# design.net
KiCad netlist of a schematic drawn in EasyEDA Pro
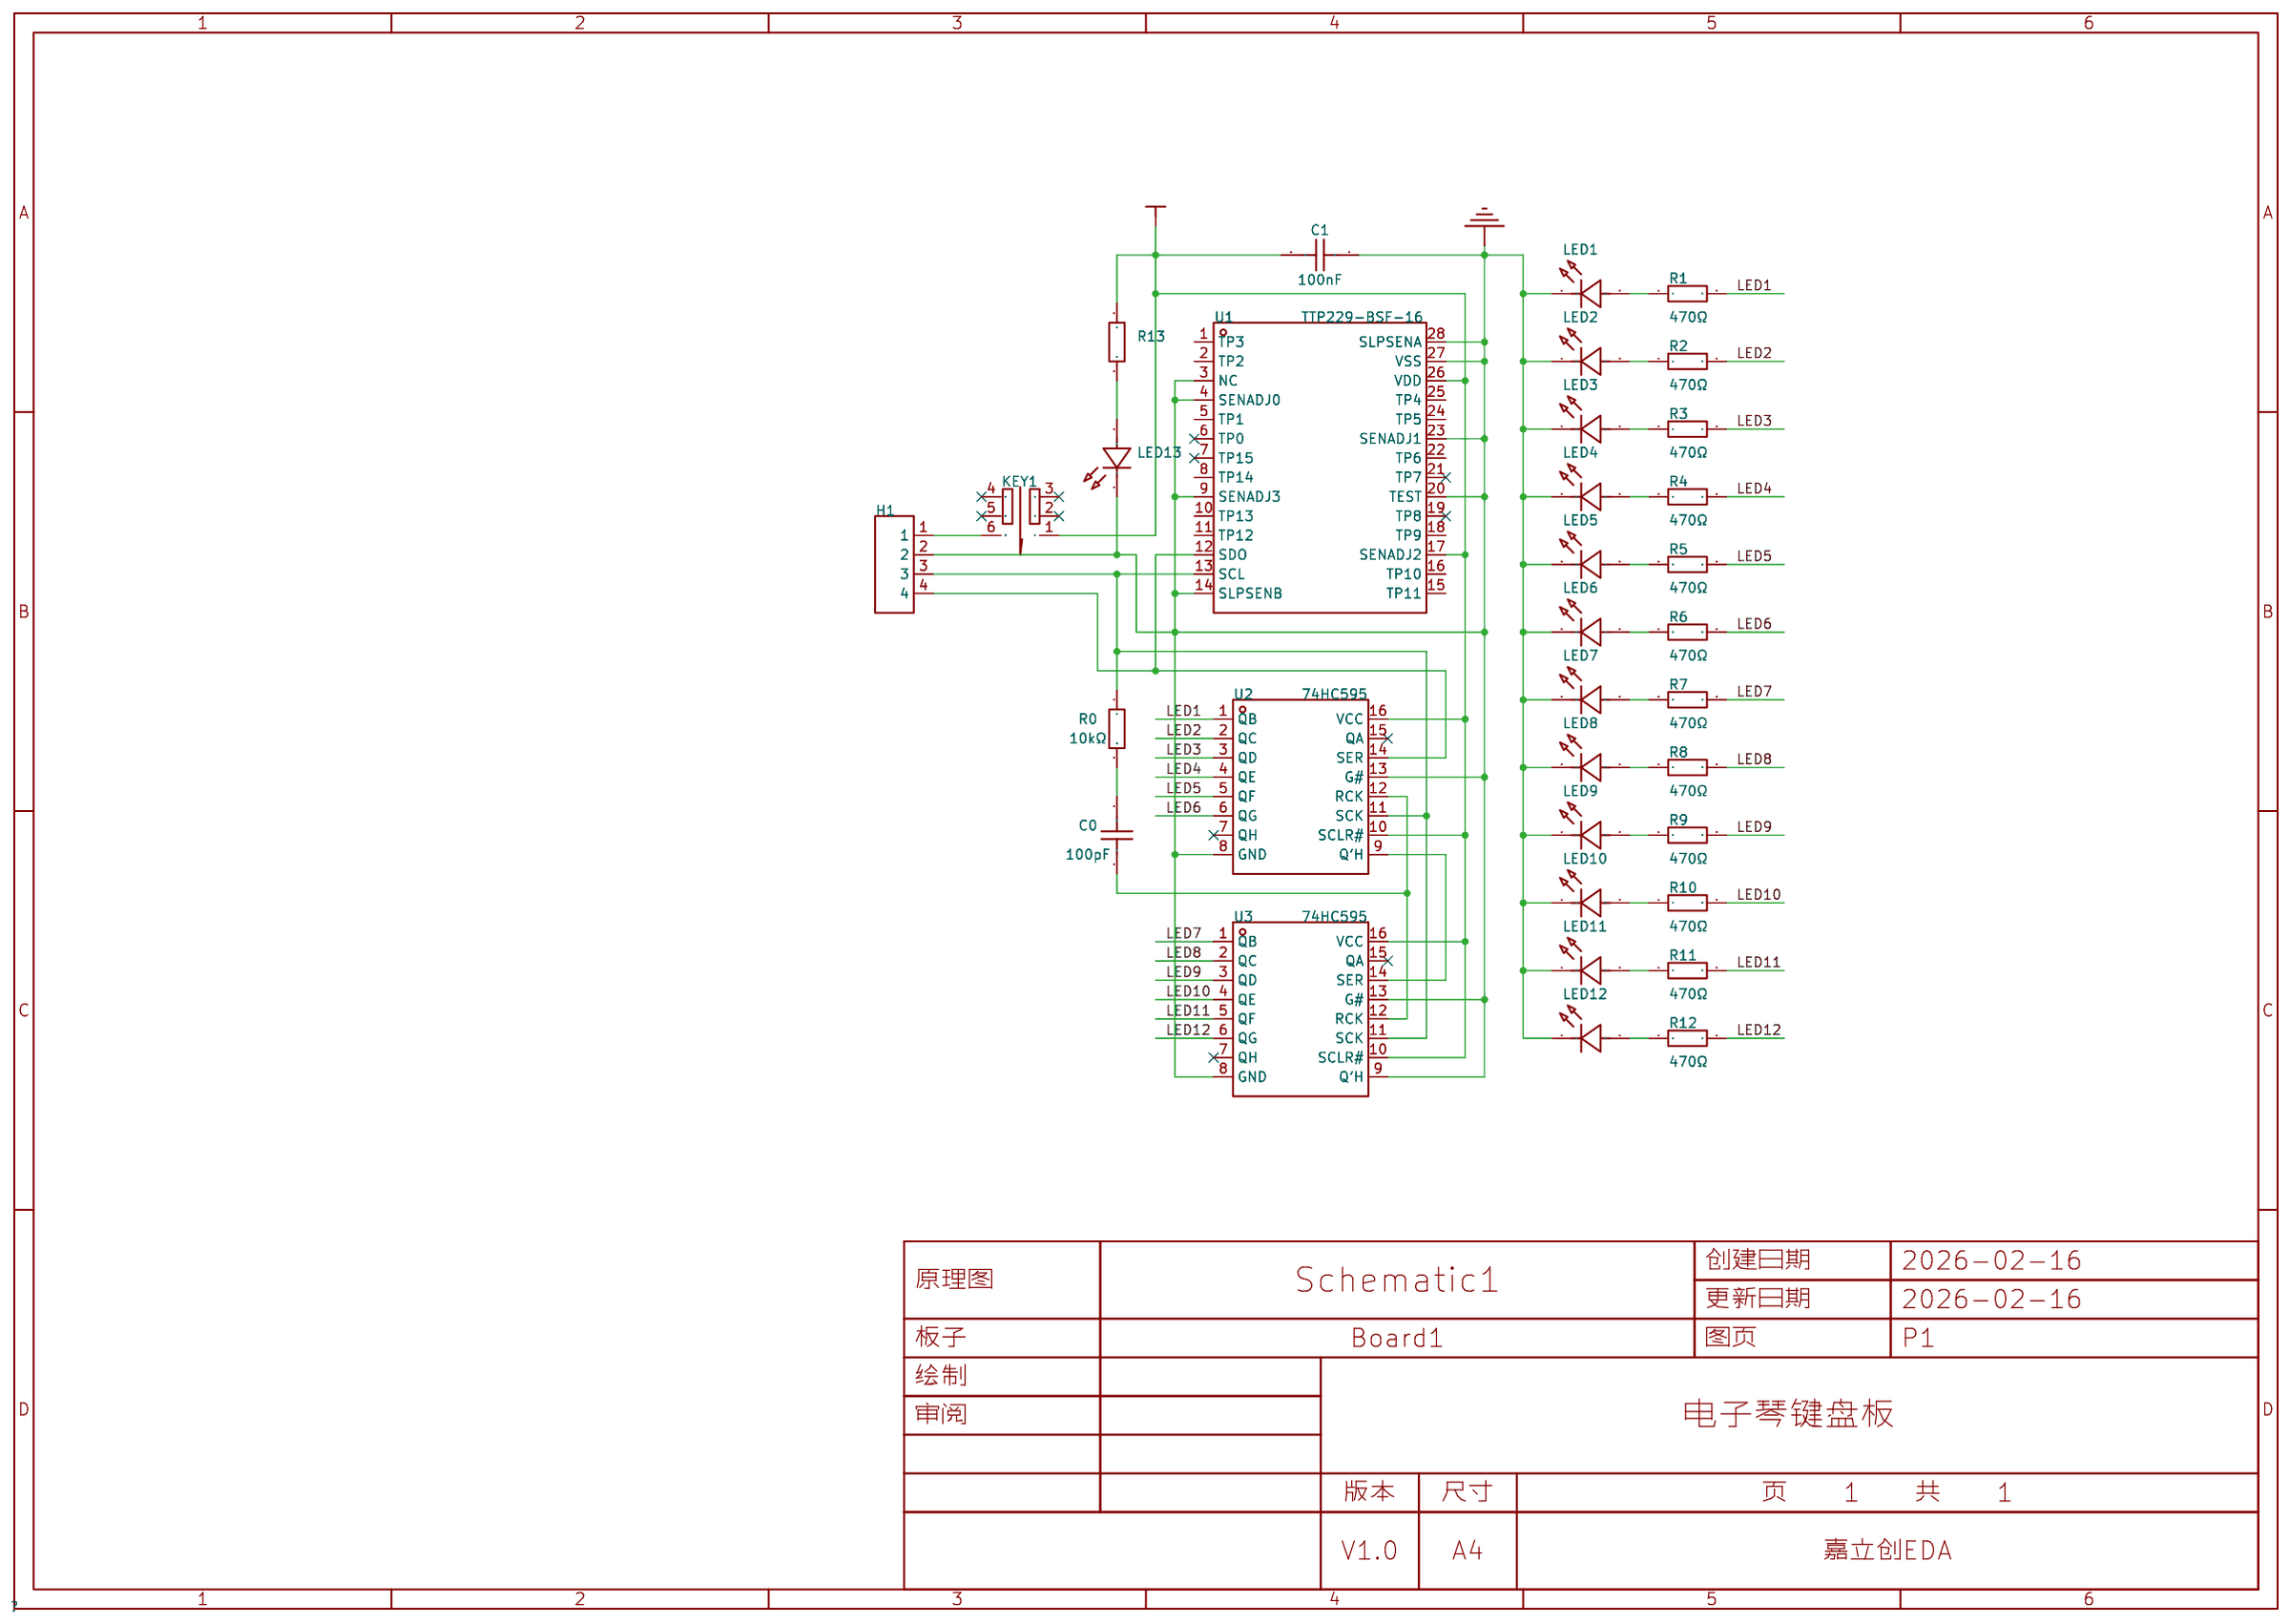
[diagram p0: schematic sheet]

(export (version "E")
  (design (tool "Eeschema 10.0.6"))
  (components
    (comp (ref "C0")
      (value "100pF")
      (footprint "easyedapro:C0603")
      (fields
        (field (name "Manufacturer Part") "CC0603JRNPO9BN101")
        (field (name "Manufacturer") "YAGEO(国巨)")
      )
      (libsource (lib "easyedapro") (part "CC0603JRNPO9BN101"))
    )
    (comp (ref "C1")
      (value "100nF")
      (footprint "easyedapro:C0603")
      (fields
        (field (name "Manufacturer Part") "CGA0603X7R104K500JT")
        (field (name "Manufacturer") "HRE(芯声)")
      )
      (libsource (lib "easyedapro") (part "CGA0603X7R104K500JT"))
    )
    (comp (ref "H1")
      (value "2.54-1*4")
      (footprint "easyedapro:HDR-TH_4P-P2.54-V-M-1")
      (fields (field (name "Manufacturer") "ZHOURI(洲日)"))
      (libsource (lib "easyedapro") (part "2.54-1*4"))
    )
    (comp (ref "KEY1")
      (value "自锁开关 5.8Z白灰白260G")
      (footprint "easyedapro:SW-TH_6P-L5.8-W5.8-P2.00-LS4.5-TR")
      (description "耐温260度")
      (libsource (lib "easyedapro") (part "Self-locking switch 5.8ZWhite and white260G"))
    )
    (comp (ref "LED1")
      (value "GL0603UB01")
      (footprint "easyedapro:LED0805-RD_GREEN")
      (fields (field (name "Manufacturer") "Guiguang light(桂光光电)"))
      (libsource (lib "easyedapro") (part "XL-2012UGC"))
    )
    (comp (ref "LED2")
      (value "GL0603UB01")
      (footprint "easyedapro:LED0805-RD_GREEN")
      (fields (field (name "Manufacturer") "Guiguang light(桂光光电)"))
      (libsource (lib "easyedapro") (part "XL-2012UGC"))
    )
    (comp (ref "LED3")
      (value "GL0603UB01")
      (footprint "easyedapro:LED0805-RD_GREEN")
      (fields (field (name "Manufacturer") "Guiguang light(桂光光电)"))
      (libsource (lib "easyedapro") (part "XL-2012UGC"))
    )
    (comp (ref "LED4")
      (value "GL0603UB01")
      (footprint "easyedapro:LED0805-RD_GREEN")
      (fields (field (name "Manufacturer") "Guiguang light(桂光光电)"))
      (libsource (lib "easyedapro") (part "XL-2012UGC"))
    )
    (comp (ref "LED5")
      (value "GL0603UB01")
      (footprint "easyedapro:LED0805-RD_GREEN")
      (fields (field (name "Manufacturer") "Guiguang light(桂光光电)"))
      (libsource (lib "easyedapro") (part "XL-2012UGC"))
    )
    (comp (ref "LED6")
      (value "GL0603UB01")
      (footprint "easyedapro:LED0805-RD_GREEN")
      (fields (field (name "Manufacturer") "Guiguang light(桂光光电)"))
      (libsource (lib "easyedapro") (part "XL-2012UGC"))
    )
    (comp (ref "LED7")
      (value "GL0603UB01")
      (footprint "easyedapro:LED0805-RD_GREEN")
      (fields (field (name "Manufacturer") "Guiguang light(桂光光电)"))
      (libsource (lib "easyedapro") (part "XL-2012UGC"))
    )
    (comp (ref "LED8")
      (value "GL0603UB01")
      (footprint "easyedapro:LED0805-RD_GREEN")
      (fields (field (name "Manufacturer") "Guiguang light(桂光光电)"))
      (libsource (lib "easyedapro") (part "XL-2012UGC"))
    )
    (comp (ref "LED9")
      (value "GL0603UB01")
      (footprint "easyedapro:LED0805-RD_GREEN")
      (fields (field (name "Manufacturer") "Guiguang light(桂光光电)"))
      (libsource (lib "easyedapro") (part "XL-2012UGC"))
    )
    (comp (ref "LED10")
      (value "GL0603UB01")
      (footprint "easyedapro:LED0805-RD_GREEN")
      (fields (field (name "Manufacturer") "Guiguang light(桂光光电)"))
      (libsource (lib "easyedapro") (part "XL-2012UGC"))
    )
    (comp (ref "LED11")
      (value "GL0603UB01")
      (footprint "easyedapro:LED0805-RD_GREEN")
      (fields (field (name "Manufacturer") "Guiguang light(桂光光电)"))
      (libsource (lib "easyedapro") (part "XL-2012UGC"))
    )
    (comp (ref "LED12")
      (value "GL0603UB01")
      (footprint "easyedapro:LED0805-RD_GREEN")
      (fields (field (name "Manufacturer") "Guiguang light(桂光光电)"))
      (libsource (lib "easyedapro") (part "XL-2012UGC"))
    )
    (comp (ref "LED13")
      (value "GL0603UB01")
      (footprint "easyedapro:LED0805-RD_GREEN")
      (fields (field (name "Manufacturer Part") "XL-2012UGC") (field (name "Manufacturer") "XINGLIGHT(成兴光)"))
      (libsource (lib "easyedapro") (part "XL-2012UGC"))
    )
    (comp (ref "R0")
      (value "10kΩ")
      (footprint "easyedapro:R0805")
      (fields
        (field (name "Manufacturer Part") "0603WAF1002T5E")
        (field (name "Manufacturer") "UNI-ROYAL(厚声)")
      )
      (libsource (lib "easyedapro") (part "电阻"))
    )
    (comp (ref "R1")
      (value "470Ω")
      (footprint "easyedapro:R0805")
      (fields
        (field (name "Manufacturer Part") "0603WAF2000T5E")
        (field (name "Manufacturer") "UNI-ROYAL(厚声)")
      )
      (libsource (lib "easyedapro") (part "电阻"))
    )
    (comp (ref "R2")
      (value "470Ω")
      (footprint "easyedapro:R0805")
      (fields
        (field (name "Manufacturer Part") "0603WAF2000T5E")
        (field (name "Manufacturer") "UNI-ROYAL(厚声)")
      )
      (libsource (lib "easyedapro") (part "电阻"))
    )
    (comp (ref "R3")
      (value "470Ω")
      (footprint "easyedapro:R0805")
      (fields
        (field (name "Manufacturer Part") "0603WAF2000T5E")
        (field (name "Manufacturer") "UNI-ROYAL(厚声)")
      )
      (libsource (lib "easyedapro") (part "电阻"))
    )
    (comp (ref "R4")
      (value "470Ω")
      (footprint "easyedapro:R0805")
      (fields
        (field (name "Manufacturer Part") "0603WAF2000T5E")
        (field (name "Manufacturer") "UNI-ROYAL(厚声)")
      )
      (libsource (lib "easyedapro") (part "电阻"))
    )
    (comp (ref "R5")
      (value "470Ω")
      (footprint "easyedapro:R0805")
      (fields
        (field (name "Manufacturer Part") "0603WAF2000T5E")
        (field (name "Manufacturer") "UNI-ROYAL(厚声)")
      )
      (libsource (lib "easyedapro") (part "电阻"))
    )
    (comp (ref "R6")
      (value "470Ω")
      (footprint "easyedapro:R0805")
      (fields
        (field (name "Manufacturer Part") "0603WAF2000T5E")
        (field (name "Manufacturer") "UNI-ROYAL(厚声)")
      )
      (libsource (lib "easyedapro") (part "电阻"))
    )
    (comp (ref "R7")
      (value "470Ω")
      (footprint "easyedapro:R0805")
      (fields
        (field (name "Manufacturer Part") "0603WAF2000T5E")
        (field (name "Manufacturer") "UNI-ROYAL(厚声)")
      )
      (libsource (lib "easyedapro") (part "电阻"))
    )
    (comp (ref "R8")
      (value "470Ω")
      (footprint "easyedapro:R0805")
      (fields
        (field (name "Manufacturer Part") "0603WAF2000T5E")
        (field (name "Manufacturer") "UNI-ROYAL(厚声)")
      )
      (libsource (lib "easyedapro") (part "电阻"))
    )
    (comp (ref "R9")
      (value "470Ω")
      (footprint "easyedapro:R0805")
      (fields
        (field (name "Manufacturer Part") "0603WAF2000T5E")
        (field (name "Manufacturer") "UNI-ROYAL(厚声)")
      )
      (libsource (lib "easyedapro") (part "电阻"))
    )
    (comp (ref "R10")
      (value "470Ω")
      (footprint "easyedapro:R0805")
      (fields
        (field (name "Manufacturer Part") "0603WAF2000T5E")
        (field (name "Manufacturer") "UNI-ROYAL(厚声)")
      )
      (libsource (lib "easyedapro") (part "电阻"))
    )
    (comp (ref "R11")
      (value "470Ω")
      (footprint "easyedapro:R0805")
      (fields
        (field (name "Manufacturer Part") "0603WAF2000T5E")
        (field (name "Manufacturer") "UNI-ROYAL(厚声)")
      )
      (libsource (lib "easyedapro") (part "电阻"))
    )
    (comp (ref "R12")
      (value "470Ω")
      (footprint "easyedapro:R0805")
      (fields
        (field (name "Manufacturer Part") "0603WAF2000T5E")
        (field (name "Manufacturer") "UNI-ROYAL(厚声)")
      )
      (libsource (lib "easyedapro") (part "电阻"))
    )
    (comp (ref "R13")
      (value "1kΩ")
      (footprint "easyedapro:R0603")
      (description "电阻类型:厚膜电阻;阻值:1kΩ;精度:±1%;功率:100mW;工作电压:75V;温度系数:±100ppm/℃;")
      (fields (field (name "Manufacturer Part") "RC0603FR-071KL") (field (name "Manufacturer") "YAGEO(国巨)"))
      (libsource (lib "easyedapro") (part "RC0603FR-071KL"))
    )
    (comp (ref "U1")
      (value "TTP229-BSF-16")
      (footprint "easyedapro:SSOP-28_L9.9-W3.9-P0.64-LS6.0-BL")
      (fields (field (name "Manufacturer") "TONTEK(通泰)"))
      (libsource (lib "easyedapro") (part "TTP229-BSF-16"))
    )
    (comp (ref "U2")
      (value "74HC595")
      (footprint "easyedapro:SOP-16_L9.9-W3.9-P1.27-LS6.0-BL")
      (fields (field (name "Manufacturer") "GR(国睿)"))
      (libsource (lib "easyedapro") (part "74HC595"))
    )
    (comp (ref "U3")
      (value "74HC595")
      (footprint "easyedapro:SOP-16_L9.9-W3.9-P1.27-LS6.0-BL")
      (fields (field (name "Manufacturer") "GR(国睿)"))
      (libsource (lib "easyedapro") (part "74HC595"))
    )
  )
  (nets
    (net (code "1") (name "/LED1") (class "Default")
      (node (ref "R1") (pin "2") (pinfunction "2_2") (pintype "input"))
      (node (ref "U2") (pin "1") (pinfunction "QB_1") (pintype "unspecified"))
    )
    (net (code "2") (name "/LED2") (class "Default")
      (node (ref "R2") (pin "2") (pinfunction "2_2") (pintype "input"))
      (node (ref "U2") (pin "2") (pinfunction "QC_2") (pintype "unspecified"))
    )
    (net (code "3") (name "/LED3") (class "Default")
      (node (ref "R3") (pin "2") (pinfunction "2_2") (pintype "input"))
      (node (ref "U2") (pin "3") (pinfunction "QD_3") (pintype "unspecified"))
    )
    (net (code "4") (name "/LED4") (class "Default")
      (node (ref "R4") (pin "2") (pinfunction "2_2") (pintype "input"))
      (node (ref "U2") (pin "4") (pinfunction "QE_4") (pintype "unspecified"))
    )
    (net (code "5") (name "/LED5") (class "Default")
      (node (ref "R5") (pin "2") (pinfunction "2_2") (pintype "input"))
      (node (ref "U2") (pin "5") (pinfunction "QF_5") (pintype "unspecified"))
    )
    (net (code "6") (name "/LED6") (class "Default")
      (node (ref "R6") (pin "2") (pinfunction "2_2") (pintype "input"))
      (node (ref "U2") (pin "6") (pinfunction "QG_6") (pintype "unspecified"))
    )
    (net (code "7") (name "/LED7") (class "Default")
      (node (ref "R7") (pin "2") (pinfunction "2_2") (pintype "input"))
      (node (ref "U3") (pin "1") (pinfunction "QB_1") (pintype "unspecified"))
    )
    (net (code "8") (name "/LED8") (class "Default")
      (node (ref "R8") (pin "2") (pinfunction "2_2") (pintype "input"))
      (node (ref "U3") (pin "2") (pinfunction "QC_2") (pintype "unspecified"))
    )
    (net (code "9") (name "/LED9") (class "Default")
      (node (ref "R9") (pin "2") (pinfunction "2_2") (pintype "input"))
      (node (ref "U3") (pin "3") (pinfunction "QD_3") (pintype "unspecified"))
    )
    (net (code "10") (name "/LED10") (class "Default")
      (node (ref "R10") (pin "2") (pinfunction "2_2") (pintype "input"))
      (node (ref "U3") (pin "4") (pinfunction "QE_4") (pintype "unspecified"))
    )
    (net (code "11") (name "/LED11") (class "Default")
      (node (ref "R11") (pin "2") (pinfunction "2_2") (pintype "input"))
      (node (ref "U3") (pin "5") (pinfunction "QF_5") (pintype "unspecified"))
    )
    (net (code "12") (name "/LED12") (class "Default")
      (node (ref "R12") (pin "2") (pinfunction "2_2") (pintype "input"))
      (node (ref "U3") (pin "6") (pinfunction "QG_6") (pintype "unspecified"))
    )
    (net (code "13") (name "GND") (class "Default")
      (node (ref "C1") (pin "1") (pinfunction "1_1") (pintype "unspecified"))
      (node (ref "H1") (pin "2") (pinfunction "2_2") (pintype "unspecified"))
      (node (ref "LED1") (pin "1") (pinfunction "K_1") (pintype "unspecified"))
      (node (ref "LED10") (pin "1") (pinfunction "K_1") (pintype "unspecified"))
      (node (ref "LED11") (pin "1") (pinfunction "K_1") (pintype "unspecified"))
      (node (ref "LED12") (pin "1") (pinfunction "K_1") (pintype "unspecified"))
      (node (ref "LED13") (pin "1") (pinfunction "K_1") (pintype "unspecified"))
      (node (ref "LED2") (pin "1") (pinfunction "K_1") (pintype "unspecified"))
      (node (ref "LED3") (pin "1") (pinfunction "K_1") (pintype "unspecified"))
      (node (ref "LED4") (pin "1") (pinfunction "K_1") (pintype "unspecified"))
      (node (ref "LED5") (pin "1") (pinfunction "K_1") (pintype "unspecified"))
      (node (ref "LED6") (pin "1") (pinfunction "K_1") (pintype "unspecified"))
      (node (ref "LED7") (pin "1") (pinfunction "K_1") (pintype "unspecified"))
      (node (ref "LED8") (pin "1") (pinfunction "K_1") (pintype "unspecified"))
      (node (ref "LED9") (pin "1") (pinfunction "K_1") (pintype "unspecified"))
      (node (ref "U1") (pin "14") (pinfunction "SLPSENB_14") (pintype "unspecified"))
      (node (ref "U1") (pin "20") (pinfunction "TEST_20") (pintype "unspecified"))
      (node (ref "U1") (pin "23") (pinfunction "SENADJ1_23") (pintype "unspecified"))
      (node (ref "U1") (pin "27") (pinfunction "VSS_27") (pintype "unspecified"))
      (node (ref "U1") (pin "28") (pinfunction "SLPSENA_28") (pintype "unspecified"))
      (node (ref "U1") (pin "3") (pinfunction "NC_3") (pintype "unspecified"))
      (node (ref "U1") (pin "4") (pinfunction "SENADJ0_4") (pintype "unspecified"))
      (node (ref "U1") (pin "9") (pinfunction "SENADJ3_9") (pintype "unspecified"))
      (node (ref "U2") (pin "13") (pinfunction "G#_13") (pintype "unspecified"))
      (node (ref "U2") (pin "8") (pinfunction "GND_8") (pintype "unspecified"))
      (node (ref "U3") (pin "13") (pinfunction "G#_13") (pintype "unspecified"))
      (node (ref "U3") (pin "8") (pinfunction "GND_8") (pintype "unspecified"))
      (node (ref "U3") (pin "9") (pinfunction "Q′H_9") (pintype "unspecified"))
    )
    (net (code "14") (name "Net-(C0-Pad1)") (class "Default")
      (node (ref "C0") (pin "1") (pinfunction "1_1") (pintype "unspecified"))
      (node (ref "R0") (pin "2") (pinfunction "2_2") (pintype "input"))
    )
    (net (code "15") (name "Net-(H1-Pad1)") (class "Default")
      (node (ref "H1") (pin "1") (pinfunction "1_1") (pintype "unspecified"))
      (node (ref "KEY1") (pin "6") (pinfunction "6_6") (pintype "input"))
    )
    (net (code "16") (name "Net-(LED1-A)") (class "Default")
      (node (ref "LED1") (pin "2") (pinfunction "A_2") (pintype "unspecified"))
      (node (ref "R1") (pin "1") (pinfunction "1_1") (pintype "input"))
    )
    (net (code "17") (name "Net-(LED2-A)") (class "Default")
      (node (ref "LED2") (pin "2") (pinfunction "A_2") (pintype "unspecified"))
      (node (ref "R2") (pin "1") (pinfunction "1_1") (pintype "input"))
    )
    (net (code "18") (name "Net-(LED3-A)") (class "Default")
      (node (ref "LED3") (pin "2") (pinfunction "A_2") (pintype "unspecified"))
      (node (ref "R3") (pin "1") (pinfunction "1_1") (pintype "input"))
    )
    (net (code "19") (name "Net-(LED4-A)") (class "Default")
      (node (ref "LED4") (pin "2") (pinfunction "A_2") (pintype "unspecified"))
      (node (ref "R4") (pin "1") (pinfunction "1_1") (pintype "input"))
    )
    (net (code "20") (name "Net-(LED5-A)") (class "Default")
      (node (ref "LED5") (pin "2") (pinfunction "A_2") (pintype "unspecified"))
      (node (ref "R5") (pin "1") (pinfunction "1_1") (pintype "input"))
    )
    (net (code "21") (name "Net-(LED6-A)") (class "Default")
      (node (ref "LED6") (pin "2") (pinfunction "A_2") (pintype "unspecified"))
      (node (ref "R6") (pin "1") (pinfunction "1_1") (pintype "input"))
    )
    (net (code "22") (name "Net-(LED7-A)") (class "Default")
      (node (ref "LED7") (pin "2") (pinfunction "A_2") (pintype "unspecified"))
      (node (ref "R7") (pin "1") (pinfunction "1_1") (pintype "input"))
    )
    (net (code "23") (name "Net-(LED8-A)") (class "Default")
      (node (ref "LED8") (pin "2") (pinfunction "A_2") (pintype "unspecified"))
      (node (ref "R8") (pin "1") (pinfunction "1_1") (pintype "input"))
    )
    (net (code "24") (name "Net-(LED9-A)") (class "Default")
      (node (ref "LED9") (pin "2") (pinfunction "A_2") (pintype "unspecified"))
      (node (ref "R9") (pin "1") (pinfunction "1_1") (pintype "input"))
    )
    (net (code "25") (name "Net-(LED10-A)") (class "Default")
      (node (ref "LED10") (pin "2") (pinfunction "A_2") (pintype "unspecified"))
      (node (ref "R10") (pin "1") (pinfunction "1_1") (pintype "input"))
    )
    (net (code "26") (name "Net-(LED11-A)") (class "Default")
      (node (ref "LED11") (pin "2") (pinfunction "A_2") (pintype "unspecified"))
      (node (ref "R11") (pin "1") (pinfunction "1_1") (pintype "input"))
    )
    (net (code "27") (name "Net-(LED12-A)") (class "Default")
      (node (ref "LED12") (pin "2") (pinfunction "A_2") (pintype "unspecified"))
      (node (ref "R12") (pin "1") (pinfunction "1_1") (pintype "input"))
    )
    (net (code "28") (name "Net-(LED13-A)") (class "Default")
      (node (ref "LED13") (pin "2") (pinfunction "A_2") (pintype "unspecified"))
      (node (ref "R13") (pin "2") (pinfunction "2_2") (pintype "input"))
    )
    (net (code "29") (name "Net-(U1-SCL)") (class "Default")
      (node (ref "H1") (pin "3") (pinfunction "3_3") (pintype "unspecified"))
      (node (ref "R0") (pin "1") (pinfunction "1_1") (pintype "input"))
      (node (ref "U1") (pin "13") (pinfunction "SCL_13") (pintype "unspecified"))
      (node (ref "U2") (pin "11") (pinfunction "SCK_11") (pintype "unspecified"))
      (node (ref "U3") (pin "11") (pinfunction "SCK_11") (pintype "unspecified"))
    )
    (net (code "30") (name "Net-(U1-SDO)") (class "Default")
      (node (ref "H1") (pin "4") (pinfunction "4_4") (pintype "unspecified"))
      (node (ref "U1") (pin "12") (pinfunction "SDO_12") (pintype "unspecified"))
      (node (ref "U2") (pin "14") (pinfunction "SER_14") (pintype "unspecified"))
    )
    (net (code "31") (name "Net-(U2-Q′H)") (class "Default")
      (node (ref "U2") (pin "9") (pinfunction "Q′H_9") (pintype "unspecified"))
      (node (ref "U3") (pin "14") (pinfunction "SER_14") (pintype "unspecified"))
    )
    (net (code "32") (name "Net-(U2-RCK)") (class "Default")
      (node (ref "C0") (pin "2") (pinfunction "2_2") (pintype "unspecified"))
      (node (ref "U2") (pin "12") (pinfunction "RCK_12") (pintype "unspecified"))
      (node (ref "U3") (pin "12") (pinfunction "RCK_12") (pintype "unspecified"))
    )
    (net (code "33") (name "VCC") (class "Default")
      (node (ref "C1") (pin "2") (pinfunction "2_2") (pintype "unspecified"))
      (node (ref "KEY1") (pin "1") (pinfunction "1_1") (pintype "input"))
      (node (ref "R13") (pin "1") (pinfunction "1_1") (pintype "input"))
      (node (ref "U1") (pin "17") (pinfunction "SENADJ2_17") (pintype "unspecified"))
      (node (ref "U1") (pin "26") (pinfunction "VDD_26") (pintype "unspecified"))
      (node (ref "U2") (pin "10") (pinfunction "SCLR#_10") (pintype "unspecified"))
      (node (ref "U2") (pin "16") (pinfunction "VCC_16") (pintype "unspecified"))
      (node (ref "U3") (pin "10") (pinfunction "SCLR#_10") (pintype "unspecified"))
      (node (ref "U3") (pin "16") (pinfunction "VCC_16") (pintype "unspecified"))
    )
    (net (code "34") (name "unconnected-(KEY1-Pad2)") (class "Default")
      (node (ref "KEY1") (pin "2") (pinfunction "2_2") (pintype "input+no_connect"))
    )
    (net (code "35") (name "unconnected-(KEY1-Pad3)") (class "Default")
      (node (ref "KEY1") (pin "3") (pinfunction "3_3") (pintype "input+no_connect"))
    )
    (net (code "36") (name "unconnected-(KEY1-Pad4)") (class "Default")
      (node (ref "KEY1") (pin "4") (pinfunction "4_4") (pintype "input+no_connect"))
    )
    (net (code "37") (name "unconnected-(KEY1-Pad5)") (class "Default")
      (node (ref "KEY1") (pin "5") (pinfunction "5_5") (pintype "input+no_connect"))
    )
    (net (code "38") (name "unconnected-(U1-TP0-Pad6)") (class "Default")
      (node (ref "U1") (pin "6") (pinfunction "TP0_6") (pintype "unspecified+no_connect"))
    )
    (net (code "39") (name "unconnected-(U1-TP1-Pad5)") (class "Default")
      (node (ref "U1") (pin "5") (pinfunction "TP1_5") (pintype "unspecified"))
    )
    (net (code "40") (name "unconnected-(U1-TP2-Pad2)") (class "Default")
      (node (ref "U1") (pin "2") (pinfunction "TP2_2") (pintype "unspecified"))
    )
    (net (code "41") (name "unconnected-(U1-TP3-Pad1)") (class "Default")
      (node (ref "U1") (pin "1") (pinfunction "TP3_1") (pintype "unspecified"))
    )
    (net (code "42") (name "unconnected-(U1-TP4-Pad25)") (class "Default")
      (node (ref "U1") (pin "25") (pinfunction "TP4_25") (pintype "unspecified"))
    )
    (net (code "43") (name "unconnected-(U1-TP5-Pad24)") (class "Default")
      (node (ref "U1") (pin "24") (pinfunction "TP5_24") (pintype "unspecified"))
    )
    (net (code "44") (name "unconnected-(U1-TP6-Pad22)") (class "Default")
      (node (ref "U1") (pin "22") (pinfunction "TP6_22") (pintype "unspecified"))
    )
    (net (code "45") (name "unconnected-(U1-TP7-Pad21)") (class "Default")
      (node (ref "U1") (pin "21") (pinfunction "TP7_21") (pintype "unspecified+no_connect"))
    )
    (net (code "46") (name "unconnected-(U1-TP8-Pad19)") (class "Default")
      (node (ref "U1") (pin "19") (pinfunction "TP8_19") (pintype "unspecified+no_connect"))
    )
    (net (code "47") (name "unconnected-(U1-TP9-Pad18)") (class "Default")
      (node (ref "U1") (pin "18") (pinfunction "TP9_18") (pintype "unspecified"))
    )
    (net (code "48") (name "unconnected-(U1-TP10-Pad16)") (class "Default")
      (node (ref "U1") (pin "16") (pinfunction "TP10_16") (pintype "unspecified"))
    )
    (net (code "49") (name "unconnected-(U1-TP11-Pad15)") (class "Default")
      (node (ref "U1") (pin "15") (pinfunction "TP11_15") (pintype "unspecified"))
    )
    (net (code "50") (name "unconnected-(U1-TP12-Pad11)") (class "Default")
      (node (ref "U1") (pin "11") (pinfunction "TP12_11") (pintype "unspecified"))
    )
    (net (code "51") (name "unconnected-(U1-TP13-Pad10)") (class "Default")
      (node (ref "U1") (pin "10") (pinfunction "TP13_10") (pintype "unspecified"))
    )
    (net (code "52") (name "unconnected-(U1-TP14-Pad8)") (class "Default")
      (node (ref "U1") (pin "8") (pinfunction "TP14_8") (pintype "unspecified"))
    )
    (net (code "53") (name "unconnected-(U1-TP15-Pad7)") (class "Default")
      (node (ref "U1") (pin "7") (pinfunction "TP15_7") (pintype "unspecified+no_connect"))
    )
    (net (code "54") (name "unconnected-(U2-QA-Pad15)") (class "Default")
      (node (ref "U2") (pin "15") (pinfunction "QA_15") (pintype "unspecified+no_connect"))
    )
    (net (code "55") (name "unconnected-(U2-QH-Pad7)") (class "Default")
      (node (ref "U2") (pin "7") (pinfunction "QH_7") (pintype "unspecified+no_connect"))
    )
    (net (code "56") (name "unconnected-(U3-QA-Pad15)") (class "Default")
      (node (ref "U3") (pin "15") (pinfunction "QA_15") (pintype "unspecified+no_connect"))
    )
    (net (code "57") (name "unconnected-(U3-QH-Pad7)") (class "Default")
      (node (ref "U3") (pin "7") (pinfunction "QH_7") (pintype "unspecified+no_connect"))
    )
  )
)
